# 2_Microcontroler_48.net
KiCad netlist of a schematic drawn in Altium Designer
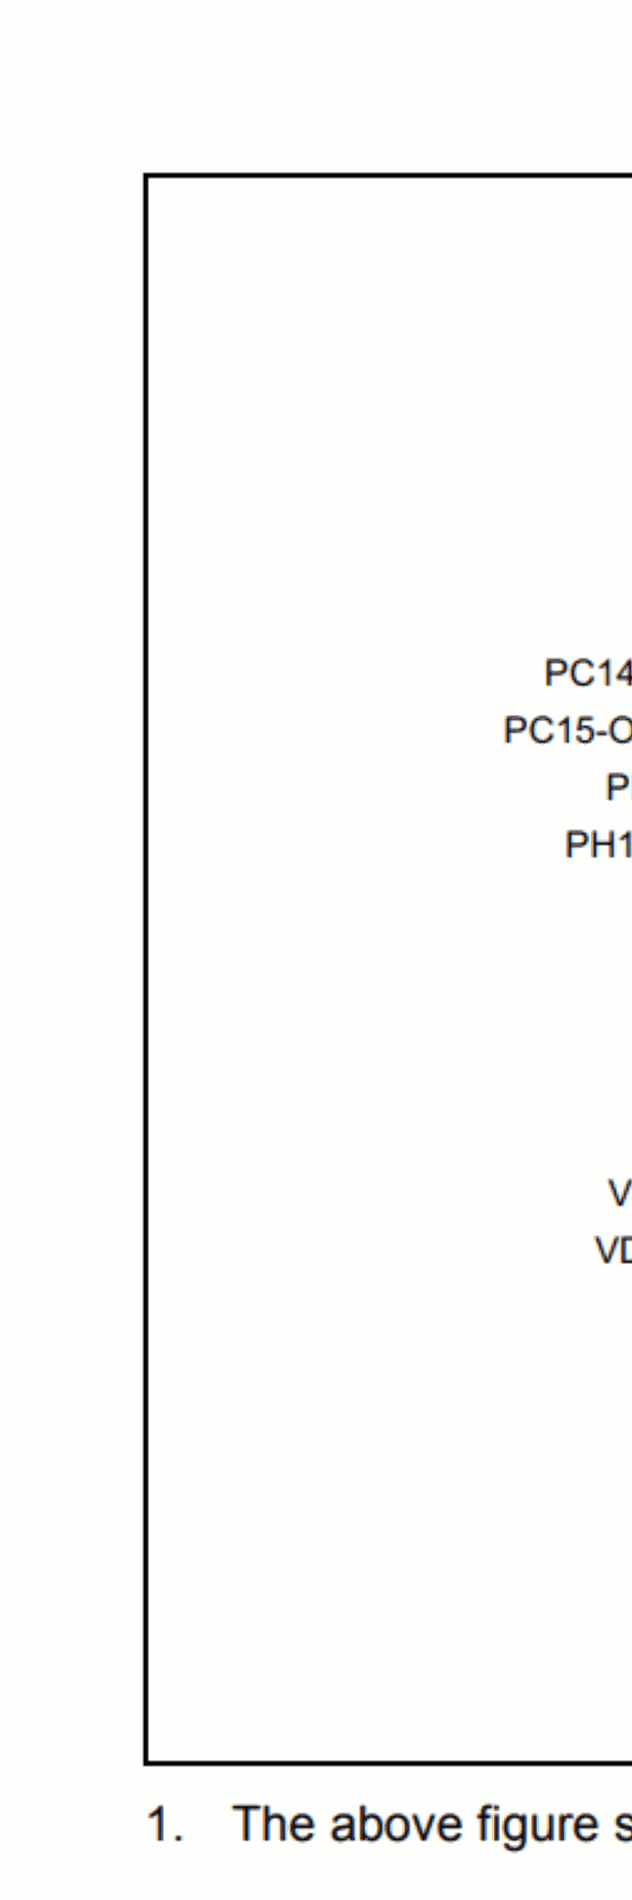
[diagram p0: 2_Microcontroler_48.SchDoc, top left]
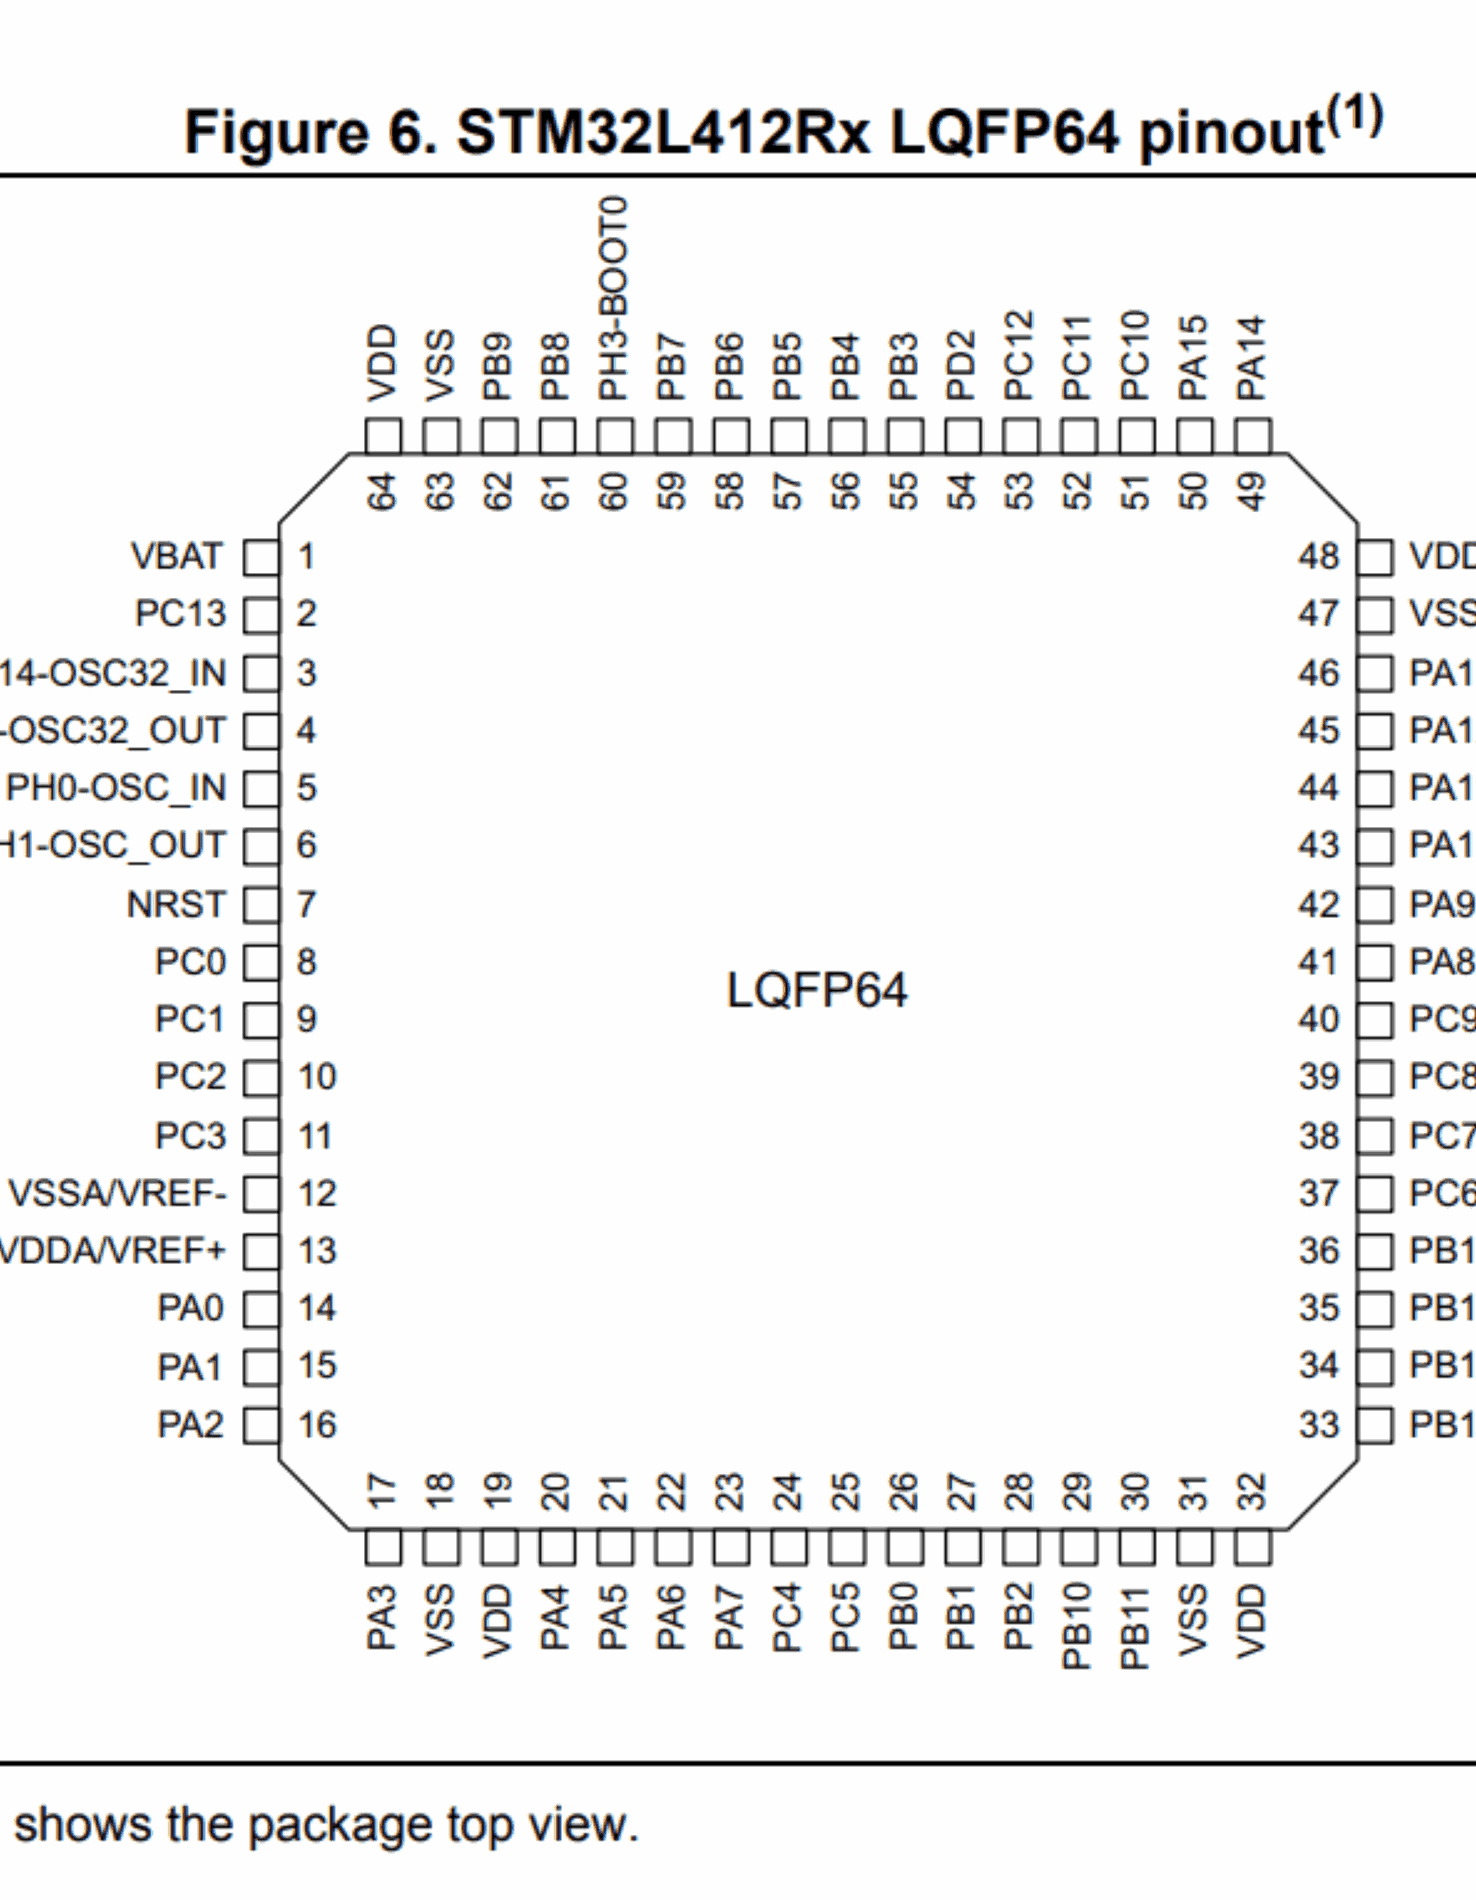
[diagram p1: 2_Microcontroler_48.SchDoc, top middle]
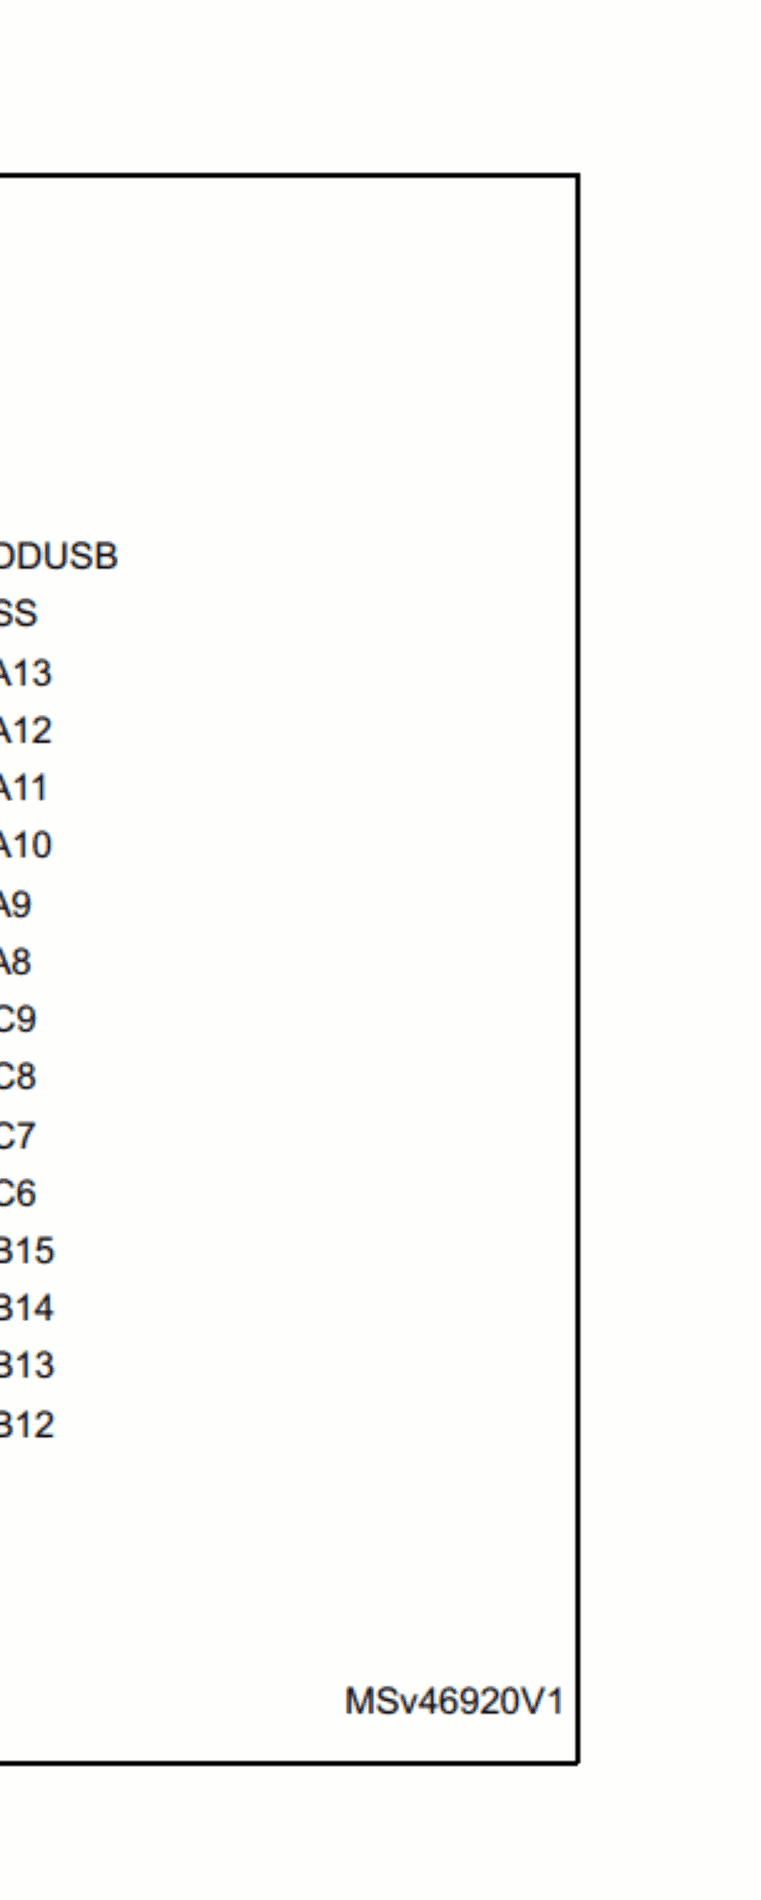
[diagram p2: 2_Microcontroler_48.SchDoc, top right]
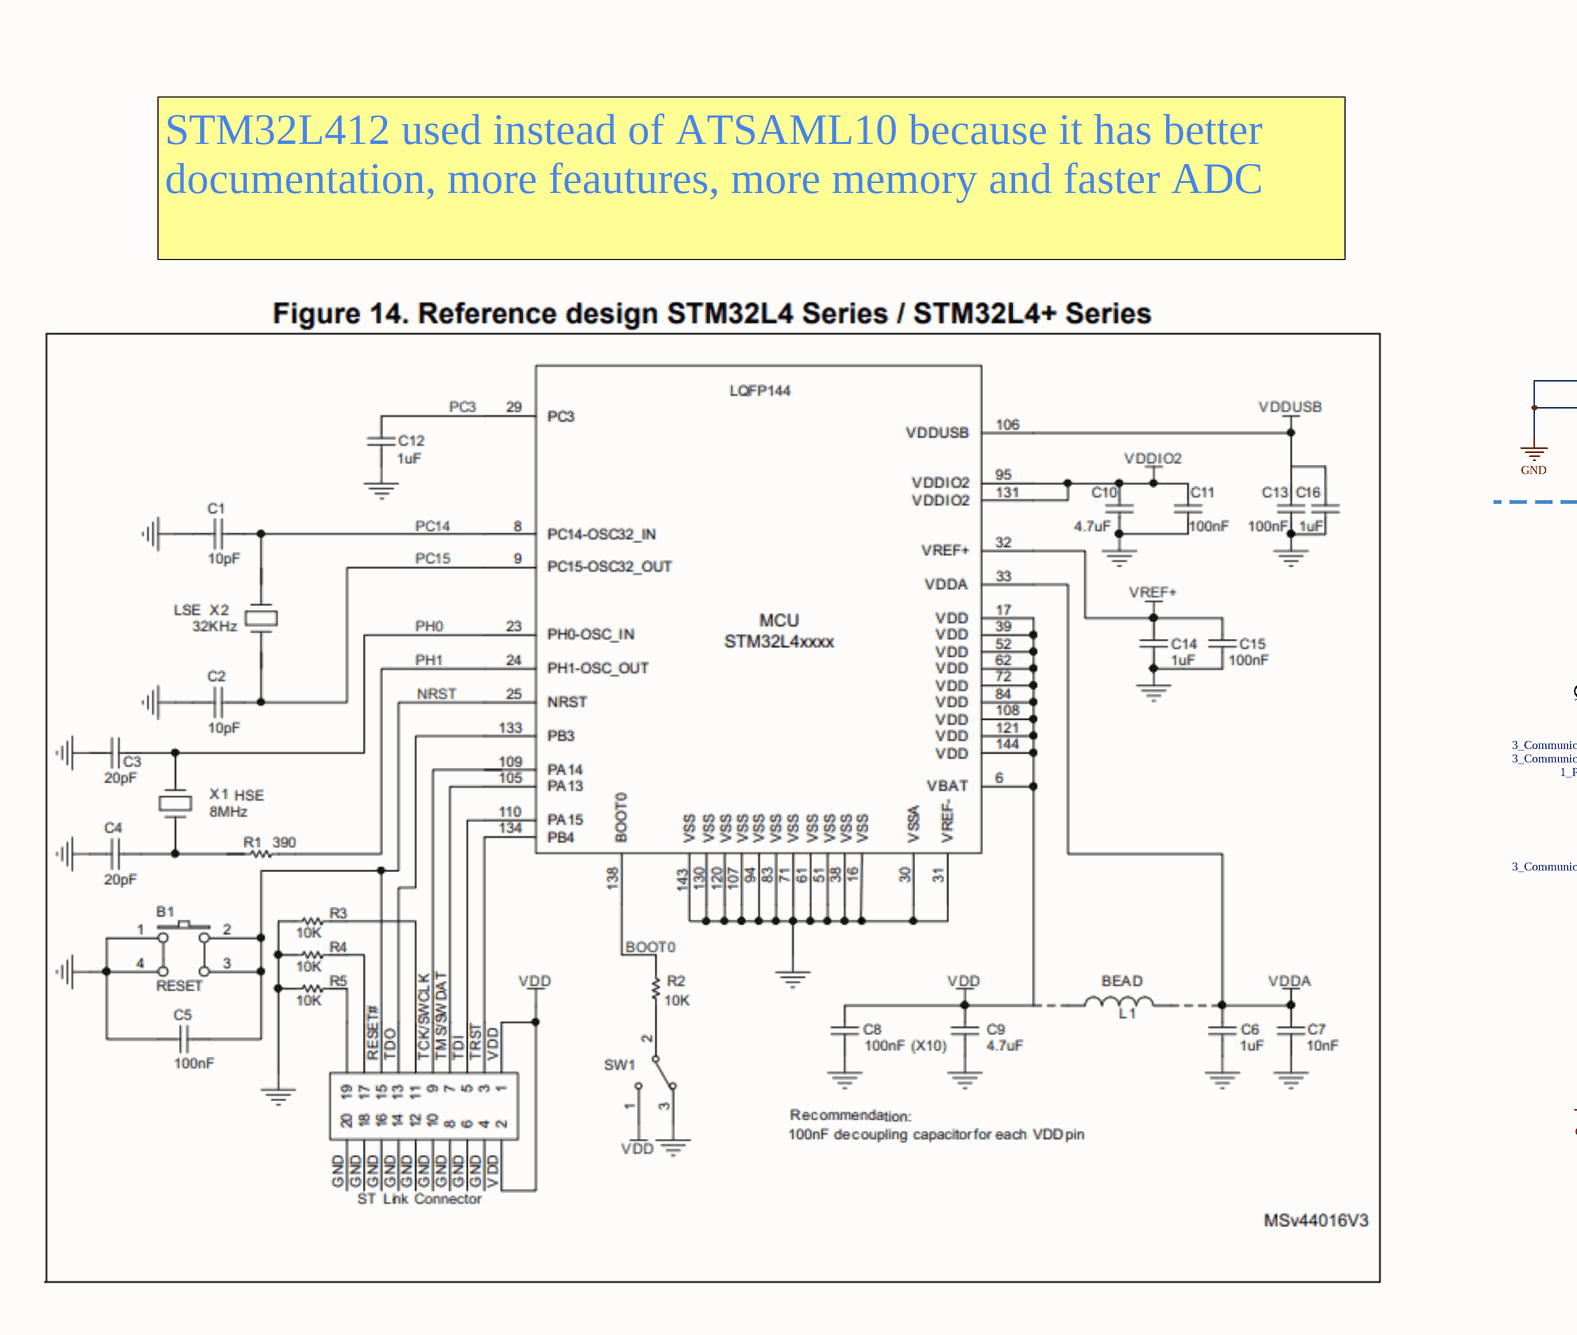
[diagram p3: 2_Microcontroler_48.SchDoc, bottom left]
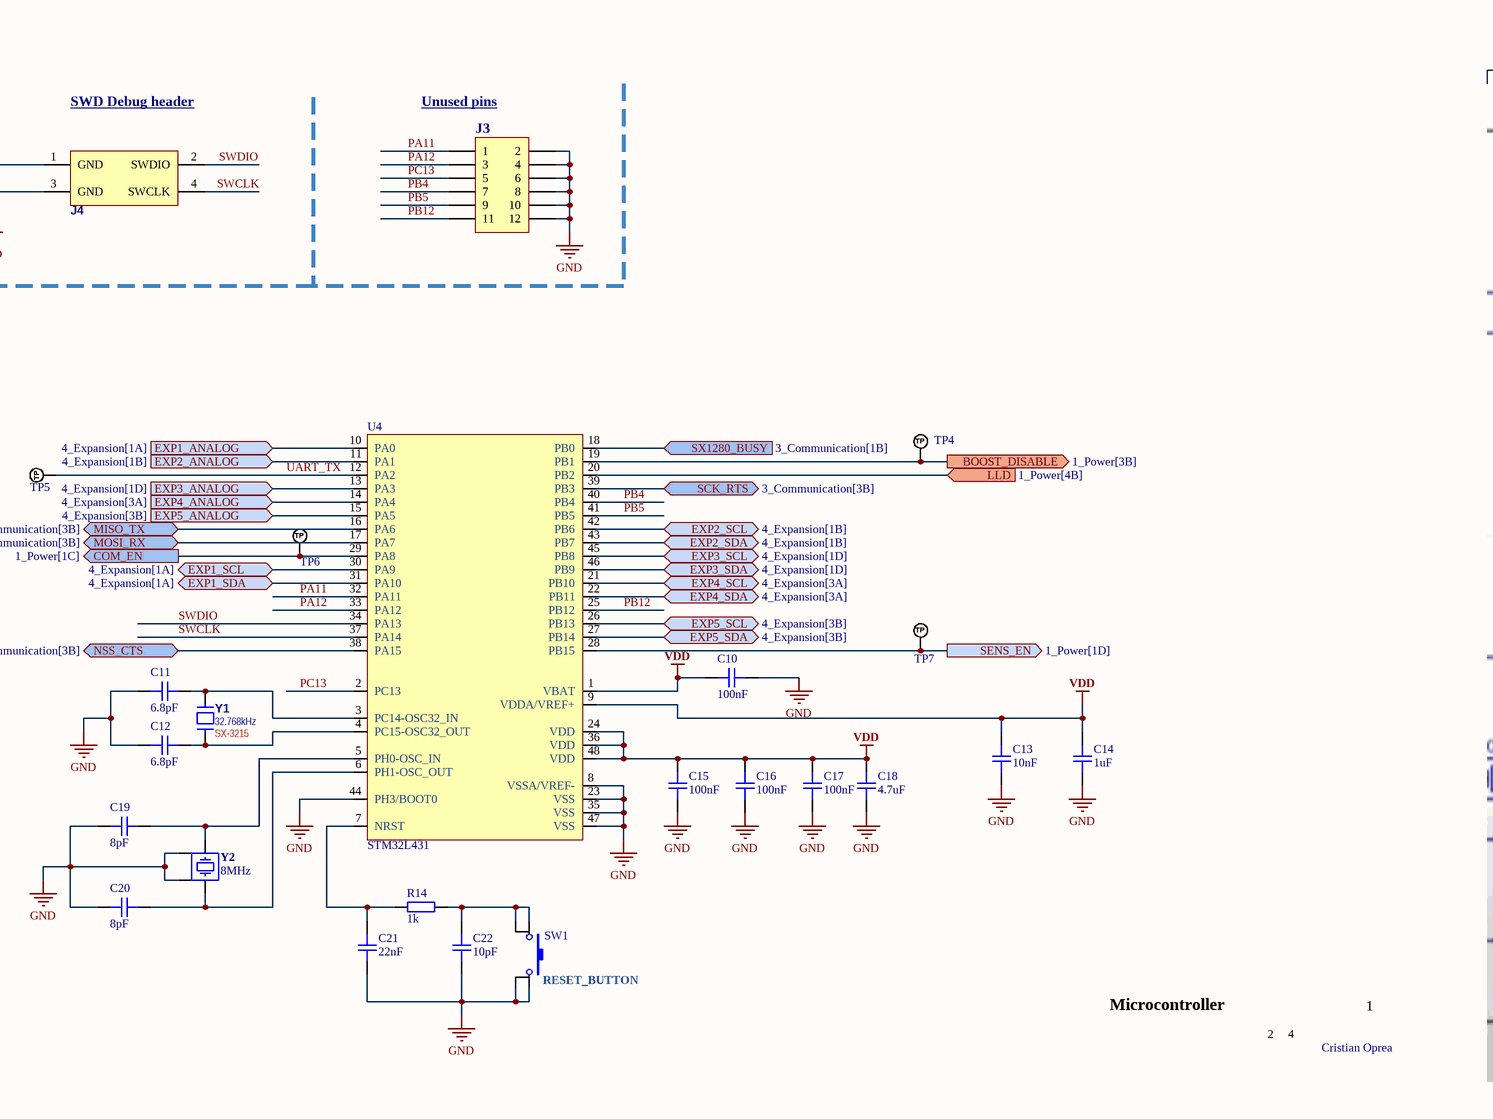
[diagram p4: 2_Microcontroler_48.SchDoc, bottom middle]
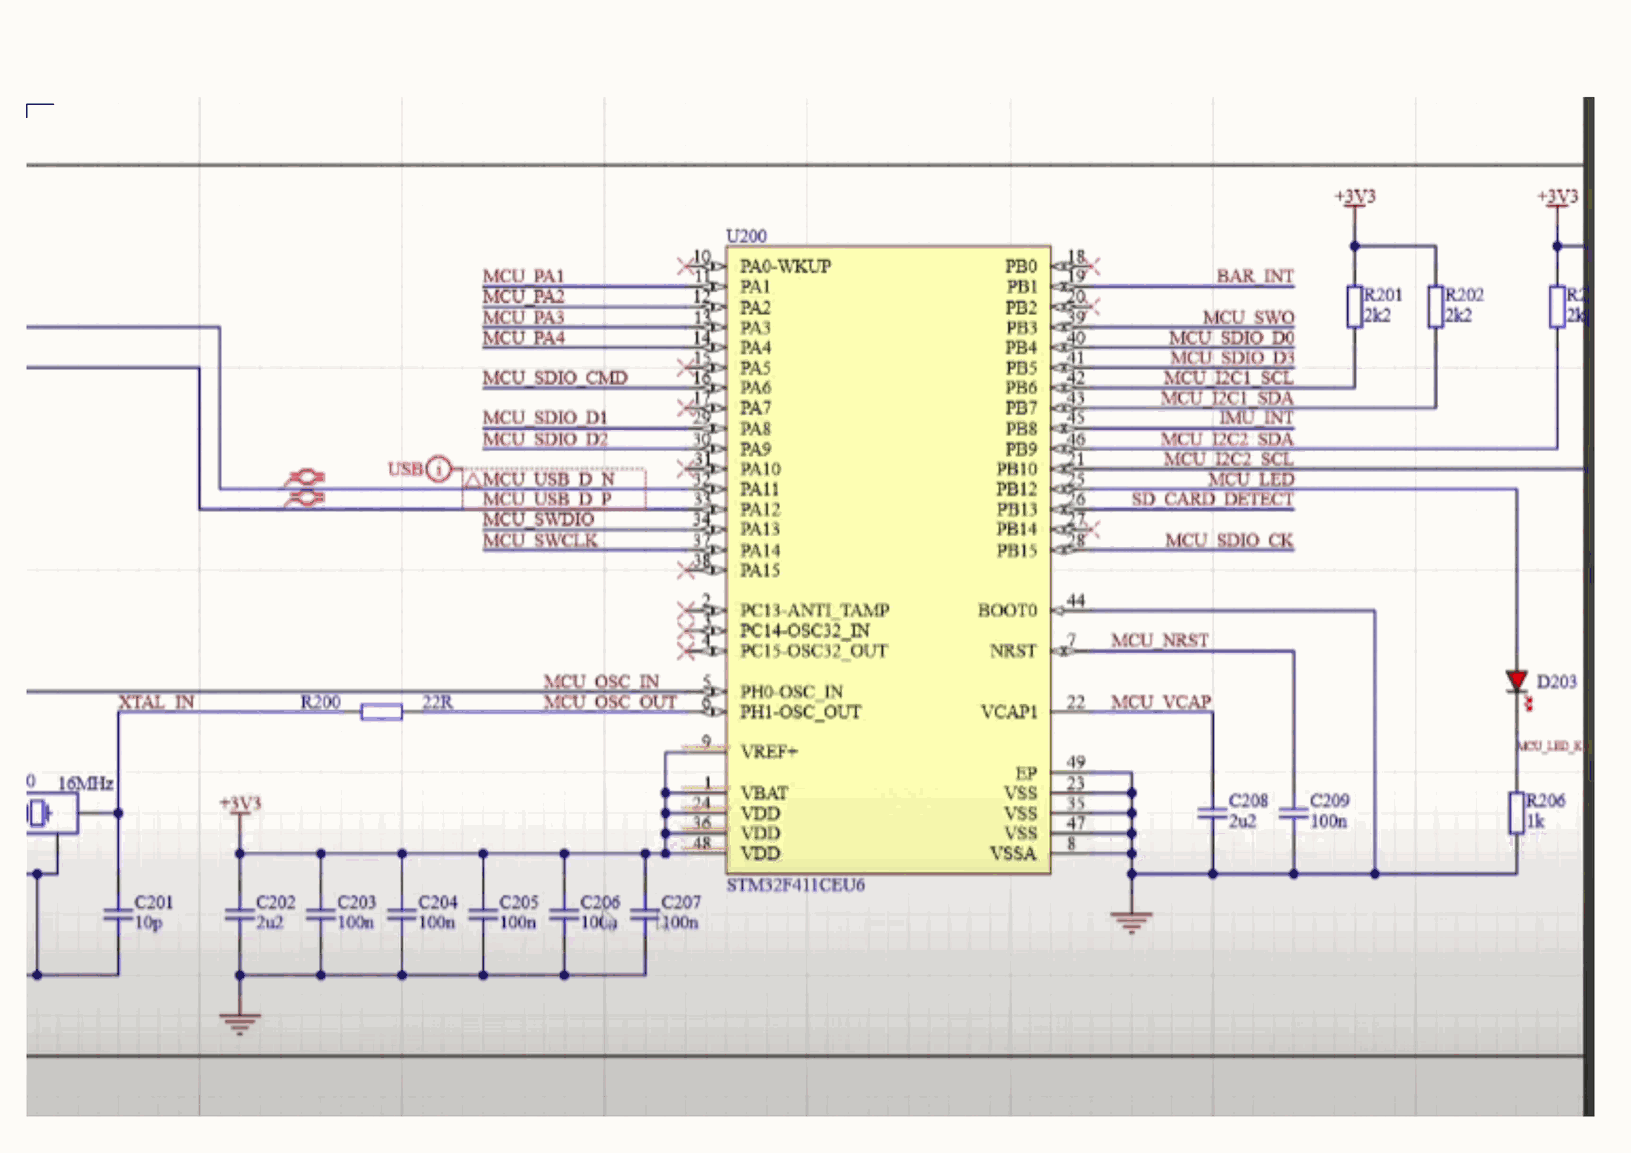
[diagram p5: 2_Microcontroler_48.SchDoc, bottom right]

(export (version "E")
  (design (tool "Eeschema 10.0.6"))
  (components
    (comp (ref "C10")
      (value "100nF")
      (footprint "C0603")
      (description "Capacitor SMD 0603")
      (libsource (lib "Schlib_H2") (part "CAP_0603"))
    )
    (comp (ref "C11")
      (value "6.8pF")
      (footprint "C0603")
      (description "Capacitor SMD 0603")
      (libsource (lib "Schlib_H2") (part "CAP_0603"))
    )
    (comp (ref "C12")
      (value "6.8pF")
      (footprint "C0603")
      (description "Capacitor SMD 0603")
      (libsource (lib "Schlib_H2") (part "CAP_0603"))
    )
    (comp (ref "C13")
      (value "10nF")
      (footprint "C0603")
      (description "Capacitor SMD 0603")
      (libsource (lib "Schlib_H2") (part "CAP_0603"))
    )
    (comp (ref "C14")
      (value "1uF")
      (footprint "C0603")
      (description "Capacitor SMD 0603")
      (libsource (lib "Schlib_H2") (part "CAP_0603"))
    )
    (comp (ref "C15")
      (value "100nF")
      (footprint "C0603")
      (description "Capacitor SMD 0603")
      (libsource (lib "Schlib_H2") (part "CAP_0603"))
    )
    (comp (ref "C16")
      (value "100nF")
      (footprint "C0603")
      (description "Capacitor SMD 0603")
      (libsource (lib "Schlib_H2") (part "CAP_0603"))
    )
    (comp (ref "C17")
      (value "100nF")
      (footprint "C0603")
      (description "Capacitor SMD 0603")
      (libsource (lib "Schlib_H2") (part "CAP_0603"))
    )
    (comp (ref "C18")
      (value "4.7uF")
      (footprint "C0603")
      (description "Capacitor SMD 0603")
      (libsource (lib "Schlib_H2") (part "CAP_0603"))
    )
    (comp (ref "C19")
      (value "8pF")
      (footprint "C0603")
      (description "Capacitor SMD 0603")
      (libsource (lib "Schlib_H2") (part "CAP_0603"))
    )
    (comp (ref "C20")
      (value "8pF")
      (footprint "C0603")
      (description "Capacitor SMD 0603")
      (libsource (lib "Schlib_H2") (part "CAP_0603"))
    )
    (comp (ref "C21")
      (value "22nF")
      (footprint "C0603")
      (description "Capacitor SMD 0603")
      (libsource (lib "Schlib_H2") (part "CAP_0603"))
    )
    (comp (ref "C22")
      (value "10pF")
      (footprint "C0603")
      (description "Capacitor SMD 0603")
      (libsource (lib "Schlib_H2") (part "CAP_0603"))
    )
    (comp (ref "J3")
      (value "Header 6X2")
      (footprint "HEADER_6x2_2.54")
      (description "Header, 12-Pin, Dual row")
      (fields (field (name "PUBLISHER") "Altium Limited"))
      (libsource (lib "Schlib_H2") (part "Header 6x2"))
    )
    (comp (ref "J4")
      (value "SWD connector")
      (footprint "HEADER_2x2_2.54")
      (description "Single Wire Debug connector with UART _TX pin")
      (libsource (lib "Schlib_H2") (part "SWD connector"))
    )
    (comp (ref "R14")
      (value "1k")
      (footprint "R0603")
      (description "Resistor SMD 0603")
      (libsource (lib "Schlib_H2") (part "RES_0603"))
    )
    (comp (ref "SW1")
      (value "PTS645SM43SMTR92 LFS")
      (footprint "SW_SKRPACE010")
      (description "Switch")
      (fields (field (name "PUBLISHER") "Altium Limited"))
      (libsource (lib "Schlib_H2") (part "SW-PB"))
    )
    (comp (ref "TP4")
      (value "TP_NOBOM")
      (footprint "TEST_PAD_THD")
      (description "Test Point Round 1mm (NO BOM)")
      (libsource (lib "Schlib_H2") (part "TEST_POINT_RND_1MM"))
    )
    (comp (ref "TP5")
      (value "TP_NOBOM")
      (footprint "TEST_PAD_THD")
      (description "Test Point Round 1mm (NO BOM)")
      (libsource (lib "Schlib_H2") (part "TEST_POINT_RND_1MM"))
    )
    (comp (ref "TP6")
      (value "TP_NOBOM")
      (footprint "TEST_PAD_THD")
      (description "Test Point Round 1mm (NO BOM)")
      (libsource (lib "Schlib_H2") (part "TEST_POINT_RND_1MM"))
    )
    (comp (ref "TP7")
      (value "TP_NOBOM")
      (footprint "TEST_PAD_THD")
      (description "Test Point Round 1mm (NO BOM)")
      (libsource (lib "Schlib_H2") (part "TEST_POINT_RND_1MM"))
    )
    (comp (ref "U4")
      (value "STM32L431")
      (footprint "QFPN-48")
      (description "Ultra-low-power Arm® Cortex®-M4 32-bit MCU+FPU, 100DMIPS,\r\n up to 128KB flash, 40KB SRAM(LQFP48)")
      (libsource (lib "Schlib_H2") (part "STM32L431"))
    )
    (comp (ref "Y1")
      (value "32.768kHz")
      (footprint "CRYSTAL_SX-3215")
      (description "Crystal")
      (fields (field (name "PACKAGEREFERENCE") "SX-3215"))
      (libsource (lib "Schlib_H2") (part "CRYSTAL_1"))
    )
    (comp (ref "Y2")
      (value "8MHz")
      (footprint "CRYSTAL_ECX-32_3.2x2.5x0.8 - duplicate")
      (description "Crystal")
      (fields
        (field (name "MANUFACTURER") "Epson")
        (field (name "MANUFACTURER PART NUMBER") "TSX-3225 24.0000MF15X-AC")
      )
      (libsource (lib "Schlib_H2") (part "Crystal"))
    )
  )
  (nets
    (net (code "1") (name "/BOOST_DISABLE") (class "Default")
      (node (ref "TP4") (pin "1") (pinfunction "TP_1") (pintype "passive"))
      (node (ref "U4") (pin "19") (pinfunction "PB1_19") (pintype "passive"))
    )
    (net (code "2") (name "/COM_EN") (class "Default")
      (node (ref "TP6") (pin "1") (pinfunction "TP_1") (pintype "passive"))
      (node (ref "U4") (pin "29") (pinfunction "PA8_29") (pintype "passive"))
    )
    (net (code "3") (name "/EXP1_ANALOG") (class "Default")
      (node (ref "U4") (pin "10") (pinfunction "PA0_10") (pintype "passive"))
    )
    (net (code "4") (name "/EXP1_SCL") (class "Default")
      (node (ref "U4") (pin "30") (pinfunction "PA9_30") (pintype "passive"))
    )
    (net (code "5") (name "/EXP1_SDA") (class "Default")
      (node (ref "U4") (pin "31") (pinfunction "PA10_31") (pintype "passive"))
    )
    (net (code "6") (name "/EXP2_ANALOG") (class "Default")
      (node (ref "U4") (pin "11") (pinfunction "PA1_11") (pintype "passive"))
    )
    (net (code "7") (name "/EXP2_SCL") (class "Default")
      (node (ref "U4") (pin "42") (pinfunction "PB6_42") (pintype "passive"))
    )
    (net (code "8") (name "/EXP2_SDA") (class "Default")
      (node (ref "U4") (pin "43") (pinfunction "PB7_43") (pintype "passive"))
    )
    (net (code "9") (name "/EXP3_ANALOG") (class "Default")
      (node (ref "U4") (pin "13") (pinfunction "PA3_13") (pintype "passive"))
    )
    (net (code "10") (name "/EXP3_SCL") (class "Default")
      (node (ref "U4") (pin "45") (pinfunction "PB8_45") (pintype "passive"))
    )
    (net (code "11") (name "/EXP3_SDA") (class "Default")
      (node (ref "U4") (pin "46") (pinfunction "PB9_46") (pintype "passive"))
    )
    (net (code "12") (name "/EXP4_ANALOG") (class "Default")
      (node (ref "U4") (pin "14") (pinfunction "PA4_14") (pintype "passive"))
    )
    (net (code "13") (name "/EXP4_SCL") (class "Default")
      (node (ref "U4") (pin "21") (pinfunction "PB10_21") (pintype "passive"))
    )
    (net (code "14") (name "/EXP4_SDA") (class "Default")
      (node (ref "U4") (pin "22") (pinfunction "PB11_22") (pintype "passive"))
    )
    (net (code "15") (name "/EXP5_ANALOG") (class "Default")
      (node (ref "U4") (pin "15") (pinfunction "PA5_15") (pintype "passive"))
    )
    (net (code "16") (name "/EXP5_SCL") (class "Default")
      (node (ref "U4") (pin "26") (pinfunction "PB13_26") (pintype "passive"))
    )
    (net (code "17") (name "/EXP5_SDA") (class "Default")
      (node (ref "U4") (pin "27") (pinfunction "PB14_27") (pintype "passive"))
    )
    (net (code "18") (name "/LLD") (class "Default")
      (node (ref "U4") (pin "20") (pinfunction "PB2_20") (pintype "passive"))
    )
    (net (code "19") (name "/MISO_TX") (class "Default")
      (node (ref "U4") (pin "16") (pinfunction "PA6_16") (pintype "passive"))
    )
    (net (code "20") (name "/MOSI_RX") (class "Default")
      (node (ref "U4") (pin "17") (pinfunction "PA7_17") (pintype "passive"))
    )
    (net (code "21") (name "/NSS_CTS") (class "Default")
      (node (ref "U4") (pin "38") (pinfunction "PA15_38") (pintype "passive"))
    )
    (net (code "22") (name "/PA11") (class "Default")
      (node (ref "J3") (pin "1") (pinfunction "1_1") (pintype "passive"))
      (node (ref "U4") (pin "32") (pinfunction "PA11_32") (pintype "passive"))
    )
    (net (code "23") (name "/PA12") (class "Default")
      (node (ref "J3") (pin "3") (pinfunction "3_3") (pintype "passive"))
      (node (ref "U4") (pin "33") (pinfunction "PA12_33") (pintype "passive"))
    )
    (net (code "24") (name "/PB4") (class "Default")
      (node (ref "J3") (pin "7") (pinfunction "7_7") (pintype "passive"))
      (node (ref "U4") (pin "40") (pinfunction "PB4_40") (pintype "passive"))
    )
    (net (code "25") (name "/PB5") (class "Default")
      (node (ref "J3") (pin "9") (pinfunction "9_9") (pintype "passive"))
      (node (ref "U4") (pin "41") (pinfunction "PB5_41") (pintype "passive"))
    )
    (net (code "26") (name "/PB12") (class "Default")
      (node (ref "J3") (pin "11") (pinfunction "11_11") (pintype "passive"))
      (node (ref "U4") (pin "25") (pinfunction "PB12_25") (pintype "passive"))
    )
    (net (code "27") (name "/PC13") (class "Default")
      (node (ref "J3") (pin "5") (pinfunction "5_5") (pintype "passive"))
      (node (ref "U4") (pin "2") (pinfunction "PC13_2") (pintype "passive"))
    )
    (net (code "28") (name "/SCK_RTS") (class "Default")
      (node (ref "U4") (pin "39") (pinfunction "PB3_39") (pintype "passive"))
    )
    (net (code "29") (name "/SENS_EN") (class "Default")
      (node (ref "TP7") (pin "1") (pinfunction "TP_1") (pintype "passive"))
      (node (ref "U4") (pin "28") (pinfunction "PB15_28") (pintype "passive"))
    )
    (net (code "30") (name "/SWCLK") (class "Default")
      (node (ref "J4") (pin "4") (pinfunction "SWCLK_4") (pintype "passive"))
      (node (ref "U4") (pin "37") (pinfunction "PA14_37") (pintype "passive"))
    )
    (net (code "31") (name "/SWDIO") (class "Default")
      (node (ref "J4") (pin "2") (pinfunction "SWDIO_2") (pintype "passive"))
      (node (ref "U4") (pin "34") (pinfunction "PA13_34") (pintype "passive"))
    )
    (net (code "32") (name "/SX1280_BUSY") (class "Default")
      (node (ref "U4") (pin "18") (pinfunction "PB0_18") (pintype "passive"))
    )
    (net (code "33") (name "/UART_TX") (class "Default")
      (node (ref "TP5") (pin "1") (pinfunction "TP_1") (pintype "passive"))
      (node (ref "U4") (pin "12") (pinfunction "PA2_12") (pintype "passive"))
    )
    (net (code "34") (name "GND") (class "Default")
      (node (ref "C10") (pin "1") (pinfunction "1_1") (pintype "passive"))
      (node (ref "C11") (pin "1") (pinfunction "1_1") (pintype "passive"))
      (node (ref "C12") (pin "1") (pinfunction "1_1") (pintype "passive"))
      (node (ref "C13") (pin "1") (pinfunction "1_1") (pintype "passive"))
      (node (ref "C14") (pin "1") (pinfunction "1_1") (pintype "passive"))
      (node (ref "C15") (pin "1") (pinfunction "1_1") (pintype "passive"))
      (node (ref "C16") (pin "1") (pinfunction "1_1") (pintype "passive"))
      (node (ref "C17") (pin "1") (pinfunction "1_1") (pintype "passive"))
      (node (ref "C18") (pin "1") (pinfunction "1_1") (pintype "passive"))
      (node (ref "C19") (pin "1") (pinfunction "1_1") (pintype "passive"))
      (node (ref "C20") (pin "1") (pinfunction "1_1") (pintype "passive"))
      (node (ref "C21") (pin "1") (pinfunction "1_1") (pintype "passive"))
      (node (ref "C22") (pin "1") (pinfunction "1_1") (pintype "passive"))
      (node (ref "J3") (pin "10") (pinfunction "10_10") (pintype "passive"))
      (node (ref "J3") (pin "12") (pinfunction "12_12") (pintype "passive"))
      (node (ref "J3") (pin "2") (pinfunction "2_2") (pintype "passive"))
      (node (ref "J3") (pin "4") (pinfunction "4_4") (pintype "passive"))
      (node (ref "J3") (pin "6") (pinfunction "6_6") (pintype "passive"))
      (node (ref "J3") (pin "8") (pinfunction "8_8") (pintype "passive"))
      (node (ref "J4") (pin "1") (pinfunction "GND_1") (pintype "passive"))
      (node (ref "J4") (pin "3") (pinfunction "GND_3") (pintype "passive"))
      (node (ref "SW1") (pin "3") (pinfunction "3_3") (pintype "passive"))
      (node (ref "SW1") (pin "4") (pinfunction "4_4") (pintype "passive"))
      (node (ref "U4") (pin "23") (pinfunction "VSS_23") (pintype "passive"))
      (node (ref "U4") (pin "35") (pinfunction "VSS_35") (pintype "passive"))
      (node (ref "U4") (pin "44") (pinfunction "PH3/BOOT0_44") (pintype "passive"))
      (node (ref "U4") (pin "47") (pinfunction "VSS_47") (pintype "passive"))
      (node (ref "U4") (pin "8") (pinfunction "VSSA/VREF-_8") (pintype "passive"))
      (node (ref "Y2") (pin "2") (pinfunction "2_2") (pintype "passive"))
      (node (ref "Y2") (pin "4") (pinfunction "4_4") (pintype "passive"))
    )
    (net (code "35") (name "Net-(C22-Pad2)") (class "Default")
      (node (ref "C22") (pin "2") (pinfunction "2_2") (pintype "passive"))
      (node (ref "R14") (pin "2") (pinfunction "2_2") (pintype "passive"))
      (node (ref "SW1") (pin "1") (pinfunction "1_1") (pintype "passive"))
      (node (ref "SW1") (pin "2") (pinfunction "2_2") (pintype "passive"))
    )
    (net (code "36") (name "Net-(U4-NRST)") (class "Default")
      (node (ref "C21") (pin "2") (pinfunction "2_2") (pintype "passive"))
      (node (ref "R14") (pin "1") (pinfunction "1_1") (pintype "passive"))
      (node (ref "U4") (pin "7") (pinfunction "NRST_7") (pintype "passive"))
    )
    (net (code "37") (name "Net-(U4-PC14-OSC32_IN)") (class "Default")
      (node (ref "C11") (pin "2") (pinfunction "2_2") (pintype "passive"))
      (node (ref "U4") (pin "3") (pinfunction "PC14-OSC32_IN_3") (pintype "passive"))
      (node (ref "Y1") (pin "2") (pinfunction "2_2") (pintype "passive"))
    )
    (net (code "38") (name "Net-(U4-PC15-OSC32_OUT)") (class "Default")
      (node (ref "C12") (pin "2") (pinfunction "2_2") (pintype "passive"))
      (node (ref "U4") (pin "4") (pinfunction "PC15-OSC32_OUT_4") (pintype "passive"))
      (node (ref "Y1") (pin "1") (pinfunction "1_1") (pintype "passive"))
    )
    (net (code "39") (name "Net-(U4-PH0-OSC_IN)") (class "Default")
      (node (ref "C19") (pin "2") (pinfunction "2_2") (pintype "passive"))
      (node (ref "U4") (pin "5") (pinfunction "PH0-OSC_IN_5") (pintype "passive"))
      (node (ref "Y2") (pin "3") (pinfunction "3_3") (pintype "passive"))
    )
    (net (code "40") (name "Net-(U4-PH1-OSC_OUT)") (class "Default")
      (node (ref "C20") (pin "2") (pinfunction "2_2") (pintype "passive"))
      (node (ref "U4") (pin "6") (pinfunction "PH1-OSC_OUT_6") (pintype "passive"))
      (node (ref "Y2") (pin "1") (pinfunction "1_1") (pintype "passive"))
    )
    (net (code "41") (name "VDD") (class "Default")
      (node (ref "C10") (pin "2") (pinfunction "2_2") (pintype "passive"))
      (node (ref "C13") (pin "2") (pinfunction "2_2") (pintype "passive"))
      (node (ref "C14") (pin "2") (pinfunction "2_2") (pintype "passive"))
      (node (ref "C15") (pin "2") (pinfunction "2_2") (pintype "passive"))
      (node (ref "C16") (pin "2") (pinfunction "2_2") (pintype "passive"))
      (node (ref "C17") (pin "2") (pinfunction "2_2") (pintype "passive"))
      (node (ref "C18") (pin "2") (pinfunction "2_2") (pintype "passive"))
      (node (ref "U4") (pin "1") (pinfunction "VBAT_1") (pintype "passive"))
      (node (ref "U4") (pin "24") (pinfunction "VDD_24") (pintype "passive"))
      (node (ref "U4") (pin "36") (pinfunction "VDD_36") (pintype "passive"))
      (node (ref "U4") (pin "48") (pinfunction "VDD_48") (pintype "passive"))
      (node (ref "U4") (pin "9") (pinfunction "VDDA/VREF+_9") (pintype "passive"))
    )
  )
)
